# z80hb3_2021-04-01.net
KiCad netlist of a schematic drawn in EasyEDA
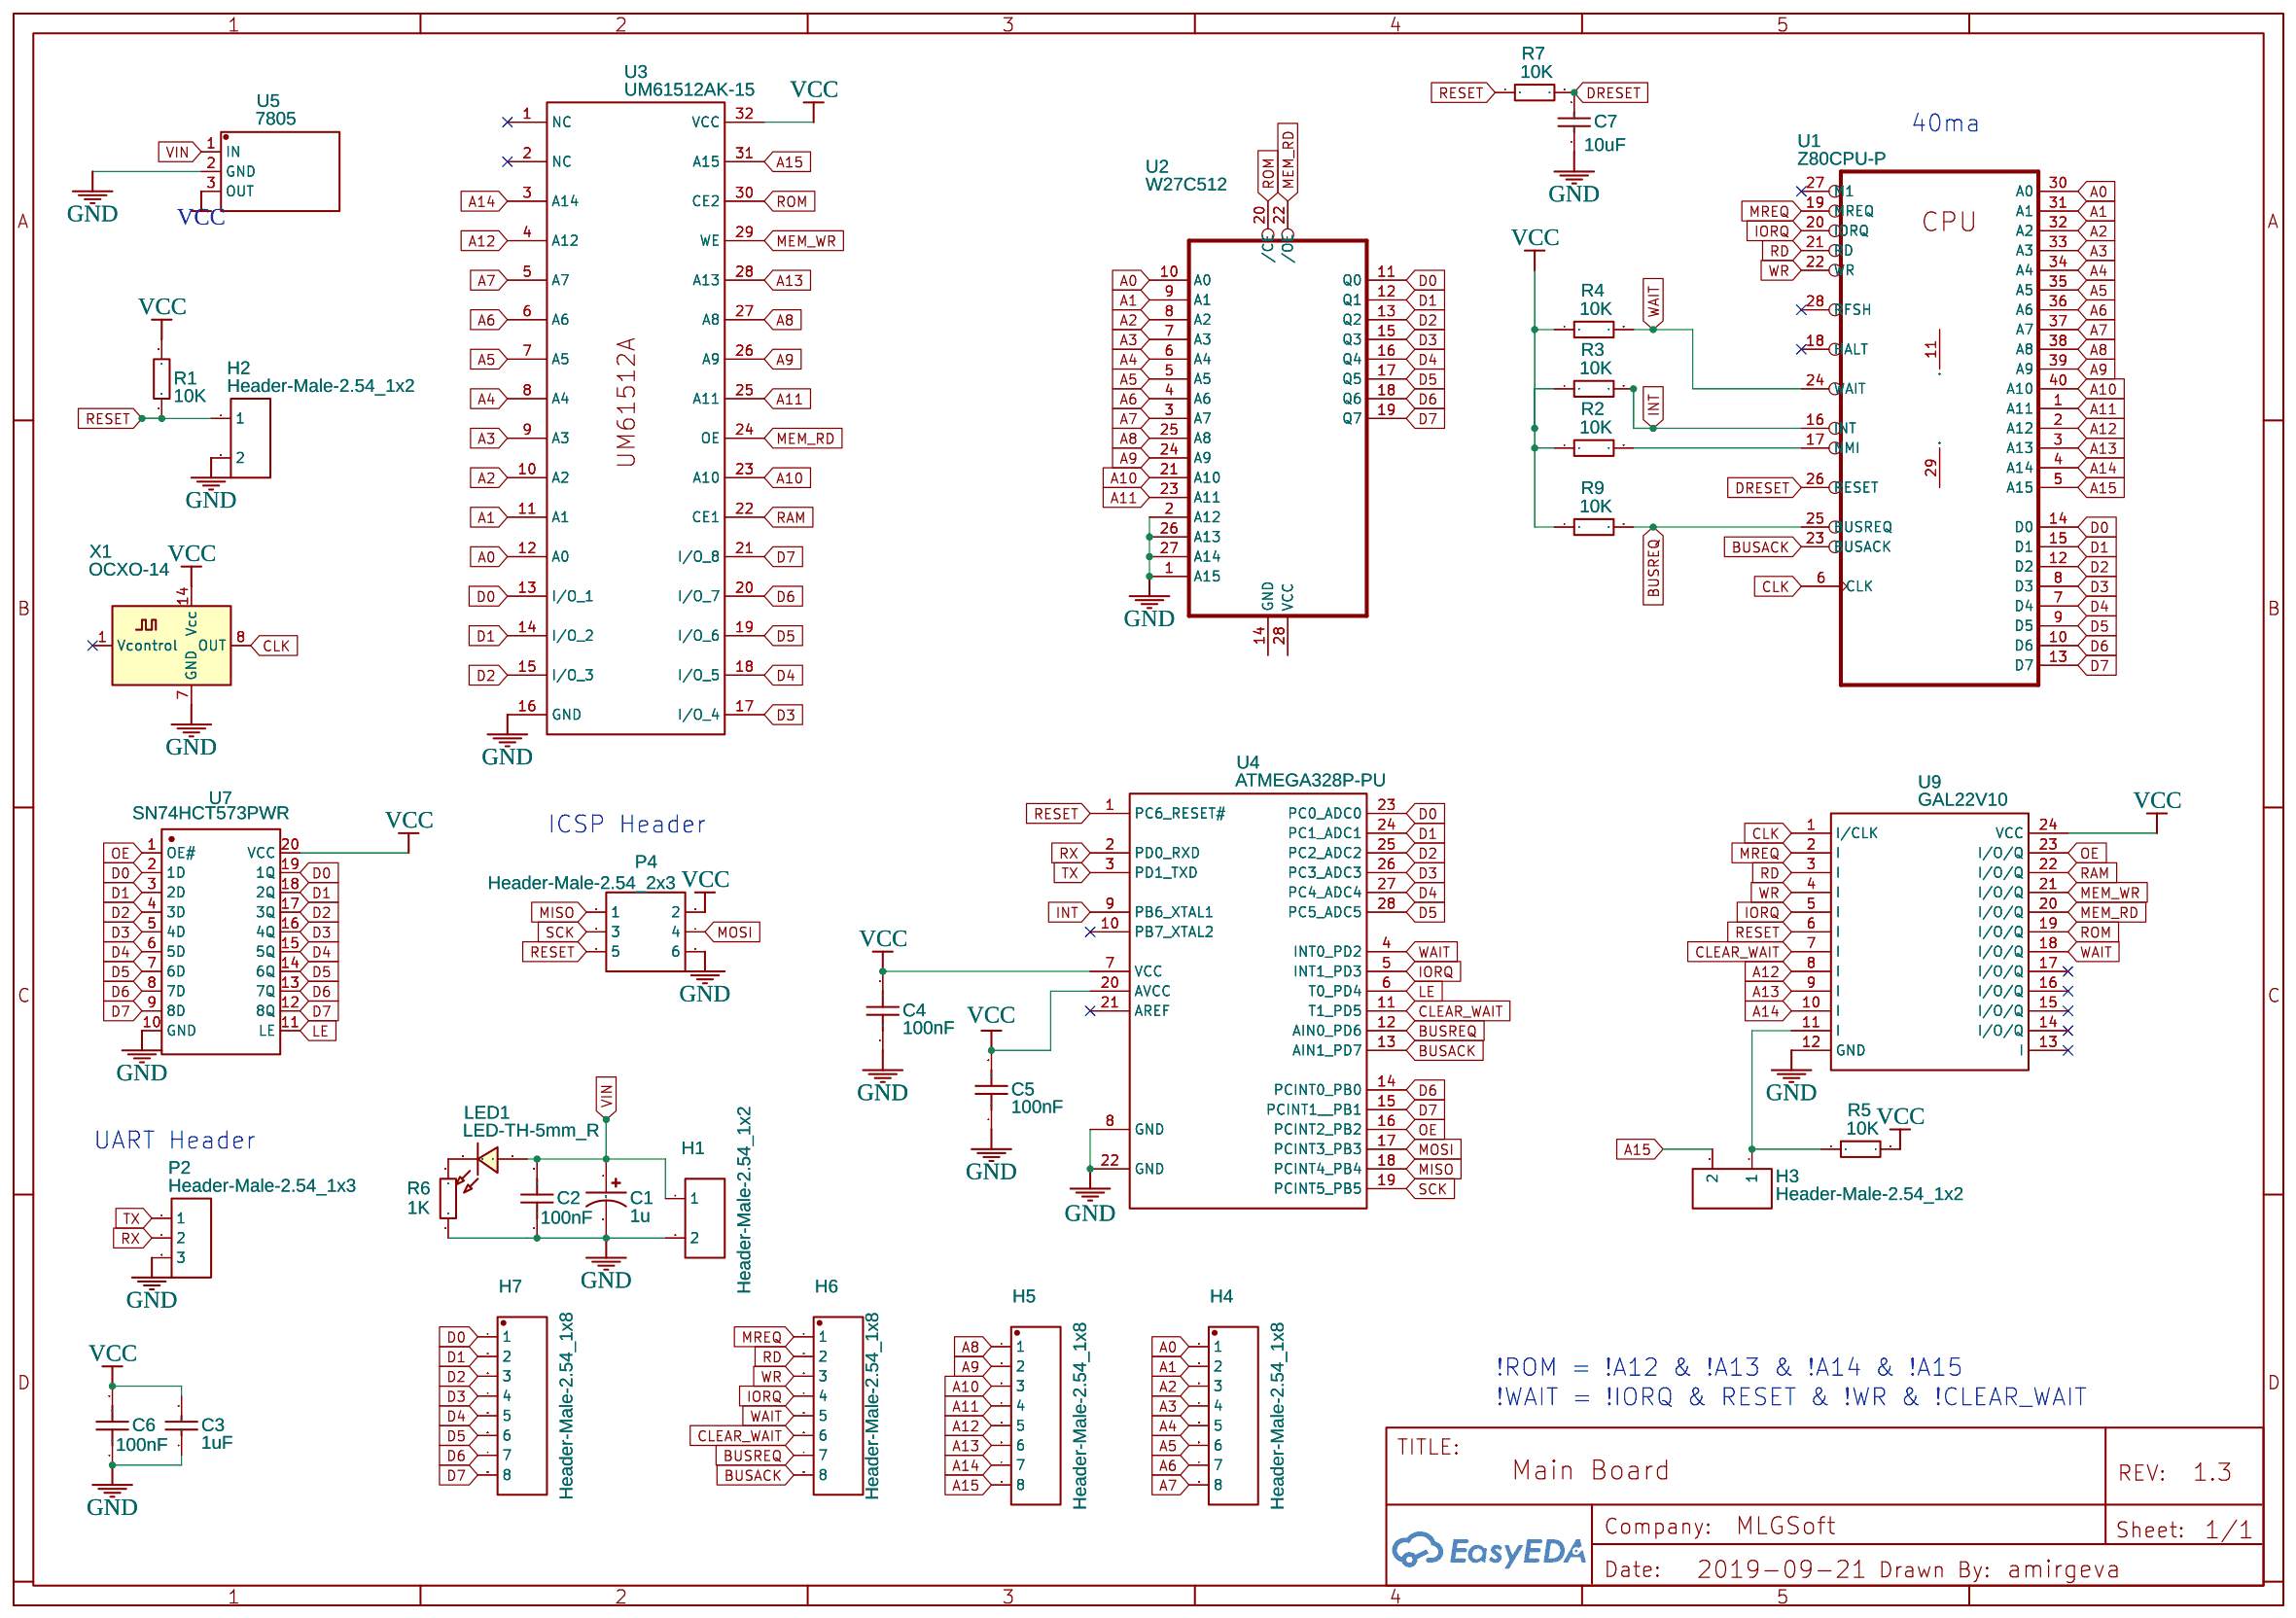
[diagram p0: schematic sheet]

(export (version "E")
  (design (tool "Eeschema 10.0.6"))
  (components
    (comp (ref "C1") (value "1u") (libsource (lib "") (part "CE_TH_D3.0×F1.5_US")))
    (comp (ref "C2")
      (value "100nF")
      (fields
        (field (name "BOM_Manufacturer Part") "0402B104K160")
        (field (name "BOM_Supplier Part") "C83056")
      )
      (libsource (lib "") (part "0402B104K160"))
    )
    (comp (ref "C3")
      (value "1uF")
      (fields
        (field (name "BOM_Manufacturer Part") "CL05A105KO5NNNC")
        (field (name "BOM_Supplier Part") "C29266")
      )
      (libsource (lib "") (part "CL05A105KO5NNNC"))
    )
    (comp (ref "C4")
      (value "100nF")
      (fields
        (field (name "BOM_Manufacturer Part") "0402B104K160")
        (field (name "BOM_Supplier Part") "C83056")
      )
      (libsource (lib "") (part "0402B104K160"))
    )
    (comp (ref "C5")
      (value "100nF")
      (fields
        (field (name "BOM_Manufacturer Part") "0402B104K160")
        (field (name "BOM_Supplier Part") "C83056")
      )
      (libsource (lib "") (part "0402B104K160"))
    )
    (comp (ref "C6")
      (value "100nF")
      (fields
        (field (name "BOM_Manufacturer Part") "0402B104K160")
        (field (name "BOM_Supplier Part") "C83056")
      )
      (libsource (lib "") (part "0402B104K160"))
    )
    (comp (ref "C7")
      (value "10uF")
      (fields
        (field (name "BOM_Manufacturer Part") "CL05A106MQ5NUNC")
        (field (name "BOM_Supplier Part") "C15525")
      )
      (libsource (lib "") (part "CL05A106MQ5NUNC"))
    )
    (comp (ref "H1")
      (value "Header-Male-2.54_1x2")
      (fields (field (name "BOM_Manufacturer Part") "826629-2") (field (name "BOM_Supplier Part") "C86471"))
      (libsource (lib "") (part "Unknown_345_610"))
    )
    (comp (ref "H2")
      (value "Header-Male-2.54_1x2")
      (fields (field (name "BOM_Manufacturer Part") "826629-2") (field (name "BOM_Supplier Part") "C86471"))
      (libsource (lib "") (part "Unknown_115_215"))
    )
    (comp (ref "H3")
      (value "Header-Male-2.54_1x2")
      (fields (field (name "BOM_Manufacturer Part") "826629-2") (field (name "BOM_Supplier Part") "C86471"))
      (libsource (lib "") (part "Unknown_870_590"))
    )
    (comp (ref "H4")
      (value "Header-Male-2.54_1x8")
      (fields
        (field (name "BOM_Manufacturer Part") "210S-1*8P L=11.6MMGold-plated black")
        (field (name "BOM_Supplier Part") "C124381")
      )
      (libsource (lib "") (part "Header-Male-2.54_1x8"))
    )
    (comp (ref "H5")
      (value "Header-Male-2.54_1x8")
      (fields
        (field (name "BOM_Manufacturer Part") "210S-1*8P L=11.6MMGold-plated black")
        (field (name "BOM_Supplier Part") "C124381")
      )
      (libsource (lib "") (part "Header-Male-2.54_1x8"))
    )
    (comp (ref "H6")
      (value "Header-Male-2.54_1x8")
      (fields
        (field (name "BOM_Manufacturer Part") "210S-1*8P L=11.6MMGold-plated black")
        (field (name "BOM_Supplier Part") "C124381")
      )
      (libsource (lib "") (part "Header-Male-2.54_1x8"))
    )
    (comp (ref "H7")
      (value "Header-Male-2.54_1x8")
      (fields
        (field (name "BOM_Manufacturer Part") "210S-1*8P L=11.6MMGold-plated black")
        (field (name "BOM_Supplier Part") "C124381")
      )
      (libsource (lib "") (part "Header-Male-2.54_1x8"))
    )
    (comp (ref "LED1")
      (value "LED-TH-5mm_R")
      (fields
        (field (name "BOM_Manufacturer Part") "333-2SURD/S530-A3")
        (field (name "BOM_Supplier Part") "C87271")
      )
      (libsource (lib "") (part "LED-TH-5mm_R"))
    )
    (comp (ref "P2")
      (value "Header-Male-2.54_1x3")
      (fields
        (field (name "BOM_Manufacturer Part") "Header2.54mm 1*3P")
        (field (name "BOM_Supplier Part") "C49257")
      )
      (libsource (lib "") (part "Unknown_85_620"))
    )
    (comp (ref "P4")
      (value "Header-Male-2.54_2x3")
      (fields (field (name "BOM_Supplier Part") "C65114"))
      (libsource (lib "") (part "Unknown_320_465"))
    )
    (comp (ref "R1")
      (value "10K")
      (fields
        (field (name "BOM_Manufacturer Part") "0402WGF1002TCE")
        (field (name "BOM_Supplier Part") "C25744")
      )
      (libsource (lib "") (part "0402WGF1002TCE_1"))
    )
    (comp (ref "R2")
      (value "10K")
      (fields
        (field (name "BOM_Manufacturer Part") "0402WGF1002TCE")
        (field (name "BOM_Supplier Part") "C25744")
      )
      (libsource (lib "") (part "0402WGF1002TCE"))
    )
    (comp (ref "R3")
      (value "10K")
      (fields
        (field (name "BOM_Manufacturer Part") "0402WGF1002TCE")
        (field (name "BOM_Supplier Part") "C25744")
      )
      (libsource (lib "") (part "0402WGF1002TCE"))
    )
    (comp (ref "R4")
      (value "10K")
      (fields
        (field (name "BOM_Manufacturer Part") "0402WGF1002TCE")
        (field (name "BOM_Supplier Part") "C25744")
      )
      (libsource (lib "") (part "0402WGF1002TCE"))
    )
    (comp (ref "R5")
      (value "10K")
      (fields
        (field (name "BOM_Manufacturer Part") "0402WGF1002TCE")
        (field (name "BOM_Supplier Part") "C25744")
      )
      (libsource (lib "") (part "0402WGF1002TCE"))
    )
    (comp (ref "R6")
      (value "1K")
      (fields
        (field (name "BOM_Manufacturer Part") "RC0402JR-071KL")
        (field (name "BOM_Supplier Part") "C105637")
      )
      (libsource (lib "") (part "RC0402JR-071KL"))
    )
    (comp (ref "R7")
      (value "10K")
      (fields
        (field (name "BOM_Manufacturer Part") "0402WGF1002TCE")
        (field (name "BOM_Supplier Part") "C25744")
      )
      (libsource (lib "") (part "0402WGF1002TCE"))
    )
    (comp (ref "R9")
      (value "10K")
      (fields
        (field (name "BOM_Manufacturer Part") "0402WGF1002TCE")
        (field (name "BOM_Supplier Part") "C25744")
      )
      (libsource (lib "") (part "0402WGF1002TCE"))
    )
    (comp (ref "U1")
      (value "Z80CPU-P")
      (fields (field (name "BOM_Manufacturer Part") "?"))
      (libsource (lib "") (part "Unknown_975_200"))
    )
    (comp (ref "U2") (value "W27C512") (libsource (lib "") (part "Unknown_635_185")))
    (comp (ref "U3") (value "UM61512AK-15") (libsource (lib "") (part "Unknown_310_215")))
    (comp (ref "U4")
      (value "ATMEGA328P-PU")
      (fields (field (name "BOM_Supplier Part") "C33901"))
      (libsource (lib "") (part "ATMEGA328P-PU"))
    )
    (comp (ref "U5")
      (value "7805")
      (fields (field (name "BOM_Supplier Part") "C305416"))
      (libsource (lib "") (part "7805"))
    )
    (comp (ref "U7")
      (value "SN74HCT573PWR")
      (fields (field (name "BOM_Supplier Part") "C141336"))
      (libsource (lib "") (part "SN74HCT573PWR"))
    )
    (comp (ref "U9") (value "GAL22V10") (libsource (lib "") (part "GAL22V10")))
    (comp (ref "X1")
      (value "OCXO-14")
      (fields (field (name "BOM_Manufacturer Part") "?"))
      (libsource (lib "") (part "Unknown_80_320"))
    )
  )
  (nets
    (net (code "1") (name "A0") (class "Default")
      (node (ref "H4") (pin "1") (pinfunction "1_1") (pintype "unspecified"))
      (node (ref "U1") (pin "30") (pinfunction "A0_30") (pintype "output"))
      (node (ref "U2") (pin "10") (pinfunction "A0_10") (pintype "input"))
      (node (ref "U3") (pin "12") (pinfunction "A0_12") (pintype "unspecified"))
    )
    (net (code "2") (name "A1") (class "Default")
      (node (ref "H4") (pin "2") (pinfunction "2_2") (pintype "unspecified"))
      (node (ref "U1") (pin "31") (pinfunction "A1_31") (pintype "output"))
      (node (ref "U2") (pin "9") (pinfunction "A1_9") (pintype "input"))
      (node (ref "U3") (pin "11") (pinfunction "A1_11") (pintype "unspecified"))
    )
    (net (code "3") (name "A2") (class "Default")
      (node (ref "H4") (pin "3") (pinfunction "3_3") (pintype "unspecified"))
      (node (ref "U1") (pin "32") (pinfunction "A2_32") (pintype "output"))
      (node (ref "U2") (pin "8") (pinfunction "A2_8") (pintype "input"))
      (node (ref "U3") (pin "10") (pinfunction "A2_10") (pintype "unspecified"))
    )
    (net (code "4") (name "A3") (class "Default")
      (node (ref "H4") (pin "4") (pinfunction "4_4") (pintype "unspecified"))
      (node (ref "U1") (pin "33") (pinfunction "A3_33") (pintype "output"))
      (node (ref "U2") (pin "7") (pinfunction "A3_7") (pintype "input"))
      (node (ref "U3") (pin "9") (pinfunction "A3_9") (pintype "unspecified"))
    )
    (net (code "5") (name "A4") (class "Default")
      (node (ref "H4") (pin "5") (pinfunction "5_5") (pintype "unspecified"))
      (node (ref "U1") (pin "34") (pinfunction "A4_34") (pintype "output"))
      (node (ref "U2") (pin "6") (pinfunction "A4_6") (pintype "input"))
      (node (ref "U3") (pin "8") (pinfunction "A4_8") (pintype "unspecified"))
    )
    (net (code "6") (name "A5") (class "Default")
      (node (ref "H4") (pin "6") (pinfunction "6_6") (pintype "unspecified"))
      (node (ref "U1") (pin "35") (pinfunction "A5_35") (pintype "output"))
      (node (ref "U2") (pin "5") (pinfunction "A5_5") (pintype "input"))
      (node (ref "U3") (pin "7") (pinfunction "A5_7") (pintype "unspecified"))
    )
    (net (code "7") (name "A6") (class "Default")
      (node (ref "H4") (pin "7") (pinfunction "7_7") (pintype "unspecified"))
      (node (ref "U1") (pin "36") (pinfunction "A6_36") (pintype "output"))
      (node (ref "U2") (pin "4") (pinfunction "A6_4") (pintype "input"))
      (node (ref "U3") (pin "6") (pinfunction "A6_6") (pintype "unspecified"))
    )
    (net (code "8") (name "A7") (class "Default")
      (node (ref "H4") (pin "8") (pinfunction "8_8") (pintype "unspecified"))
      (node (ref "U1") (pin "37") (pinfunction "A7_37") (pintype "output"))
      (node (ref "U2") (pin "3") (pinfunction "A7_3") (pintype "input"))
      (node (ref "U3") (pin "5") (pinfunction "A7_5") (pintype "unspecified"))
    )
    (net (code "9") (name "A8") (class "Default")
      (node (ref "H5") (pin "1") (pinfunction "1_1") (pintype "unspecified"))
      (node (ref "U1") (pin "38") (pinfunction "A8_38") (pintype "output"))
      (node (ref "U2") (pin "25") (pinfunction "A8_25") (pintype "input"))
      (node (ref "U3") (pin "27") (pinfunction "A8_27") (pintype "unspecified"))
    )
    (net (code "10") (name "A9") (class "Default")
      (node (ref "H5") (pin "2") (pinfunction "2_2") (pintype "unspecified"))
      (node (ref "U1") (pin "39") (pinfunction "A9_39") (pintype "output"))
      (node (ref "U2") (pin "24") (pinfunction "A9_24") (pintype "input"))
      (node (ref "U3") (pin "26") (pinfunction "A9_26") (pintype "unspecified"))
    )
    (net (code "11") (name "A10") (class "Default")
      (node (ref "H5") (pin "3") (pinfunction "3_3") (pintype "unspecified"))
      (node (ref "U1") (pin "40") (pinfunction "A10_40") (pintype "output"))
      (node (ref "U2") (pin "21") (pinfunction "A10_21") (pintype "input"))
      (node (ref "U3") (pin "23") (pinfunction "A10_23") (pintype "unspecified"))
    )
    (net (code "12") (name "A11") (class "Default")
      (node (ref "H5") (pin "4") (pinfunction "4_4") (pintype "unspecified"))
      (node (ref "U1") (pin "1") (pinfunction "A11_1") (pintype "output"))
      (node (ref "U2") (pin "23") (pinfunction "A11_23") (pintype "input"))
      (node (ref "U3") (pin "25") (pinfunction "A11_25") (pintype "unspecified"))
    )
    (net (code "13") (name "A12") (class "Default")
      (node (ref "H5") (pin "5") (pinfunction "5_5") (pintype "unspecified"))
      (node (ref "U1") (pin "2") (pinfunction "A12_2") (pintype "output"))
      (node (ref "U3") (pin "4") (pinfunction "A12_4") (pintype "unspecified"))
      (node (ref "U9") (pin "8") (pinfunction "I_8") (pintype "unspecified"))
    )
    (net (code "14") (name "A13") (class "Default")
      (node (ref "H5") (pin "6") (pinfunction "6_6") (pintype "unspecified"))
      (node (ref "U1") (pin "3") (pinfunction "A13_3") (pintype "output"))
      (node (ref "U3") (pin "28") (pinfunction "A13_28") (pintype "unspecified"))
      (node (ref "U9") (pin "9") (pinfunction "I_9") (pintype "unspecified"))
    )
    (net (code "15") (name "A14") (class "Default")
      (node (ref "H5") (pin "7") (pinfunction "7_7") (pintype "unspecified"))
      (node (ref "U1") (pin "4") (pinfunction "A14_4") (pintype "output"))
      (node (ref "U3") (pin "3") (pinfunction "A14_3") (pintype "unspecified"))
      (node (ref "U9") (pin "10") (pinfunction "I_10") (pintype "unspecified"))
    )
    (net (code "16") (name "A15") (class "Default")
      (node (ref "H3") (pin "2") (pinfunction "2_2") (pintype "unspecified"))
      (node (ref "H5") (pin "8") (pinfunction "8_8") (pintype "unspecified"))
      (node (ref "U1") (pin "5") (pinfunction "A15_5") (pintype "output"))
      (node (ref "U3") (pin "31") (pinfunction "A15_31") (pintype "unspecified"))
    )
    (net (code "17") (name "BUSACK") (class "Default")
      (node (ref "H6") (pin "8") (pinfunction "8_8") (pintype "unspecified"))
      (node (ref "U1") (pin "23") (pinfunction "BUSACK_23") (pintype "output"))
      (node (ref "U4") (pin "13") (pinfunction "AIN1_PD7_13") (pintype "bidirectional"))
    )
    (net (code "18") (name "BUSREQ") (class "Default")
      (node (ref "H6") (pin "7") (pinfunction "7_7") (pintype "unspecified"))
      (node (ref "R9") (pin "2") (pinfunction "2_2") (pintype "input"))
      (node (ref "U1") (pin "25") (pinfunction "BUSREQ_25") (pintype "input"))
      (node (ref "U4") (pin "12") (pinfunction "AIN0_PD6_12") (pintype "bidirectional"))
    )
    (net (code "19") (name "CLEAR_WAIT") (class "Default")
      (node (ref "H6") (pin "6") (pinfunction "6_6") (pintype "unspecified"))
      (node (ref "U4") (pin "11") (pinfunction "T1_PD5_11") (pintype "bidirectional"))
      (node (ref "U9") (pin "7") (pinfunction "I_7") (pintype "unspecified"))
    )
    (net (code "20") (name "CLK") (class "Default")
      (node (ref "U1") (pin "6") (pinfunction "CLK_6") (pintype "input"))
      (node (ref "U9") (pin "1") (pinfunction "I/CLK_1") (pintype "unspecified"))
      (node (ref "X1") (pin "8") (pinfunction "OUT_8") (pintype "output"))
    )
    (net (code "21") (name "D0") (class "Default")
      (node (ref "H7") (pin "1") (pinfunction "1_1") (pintype "unspecified"))
      (node (ref "U1") (pin "14") (pinfunction "D0_14") (pintype "unspecified"))
      (node (ref "U2") (pin "11") (pinfunction "Q0_11") (pintype "bidirectional"))
      (node (ref "U3") (pin "13") (pinfunction "I/O_1_13") (pintype "unspecified"))
      (node (ref "U4") (pin "23") (pinfunction "PC0_ADC0_23") (pintype "bidirectional"))
      (node (ref "U7") (pin "19") (pinfunction "1Q_19") (pintype "unspecified"))
      (node (ref "U7") (pin "2") (pinfunction "1D_2") (pintype "unspecified"))
    )
    (net (code "22") (name "D1") (class "Default")
      (node (ref "H7") (pin "2") (pinfunction "2_2") (pintype "unspecified"))
      (node (ref "U1") (pin "15") (pinfunction "D1_15") (pintype "unspecified"))
      (node (ref "U2") (pin "12") (pinfunction "Q1_12") (pintype "bidirectional"))
      (node (ref "U3") (pin "14") (pinfunction "I/O_2_14") (pintype "unspecified"))
      (node (ref "U4") (pin "24") (pinfunction "PC1_ADC1_24") (pintype "bidirectional"))
      (node (ref "U7") (pin "18") (pinfunction "2Q_18") (pintype "unspecified"))
      (node (ref "U7") (pin "3") (pinfunction "2D_3") (pintype "unspecified"))
    )
    (net (code "23") (name "D2") (class "Default")
      (node (ref "H7") (pin "3") (pinfunction "3_3") (pintype "unspecified"))
      (node (ref "U1") (pin "12") (pinfunction "D2_12") (pintype "unspecified"))
      (node (ref "U2") (pin "13") (pinfunction "Q2_13") (pintype "bidirectional"))
      (node (ref "U3") (pin "15") (pinfunction "I/O_3_15") (pintype "unspecified"))
      (node (ref "U4") (pin "25") (pinfunction "PC2_ADC2_25") (pintype "bidirectional"))
      (node (ref "U7") (pin "17") (pinfunction "3Q_17") (pintype "unspecified"))
      (node (ref "U7") (pin "4") (pinfunction "3D_4") (pintype "unspecified"))
    )
    (net (code "24") (name "D3") (class "Default")
      (node (ref "H7") (pin "4") (pinfunction "4_4") (pintype "unspecified"))
      (node (ref "U1") (pin "8") (pinfunction "D3_8") (pintype "unspecified"))
      (node (ref "U2") (pin "15") (pinfunction "Q3_15") (pintype "bidirectional"))
      (node (ref "U3") (pin "17") (pinfunction "I/O_4_17") (pintype "unspecified"))
      (node (ref "U4") (pin "26") (pinfunction "PC3_ADC3_26") (pintype "bidirectional"))
      (node (ref "U7") (pin "16") (pinfunction "4Q_16") (pintype "unspecified"))
      (node (ref "U7") (pin "5") (pinfunction "4D_5") (pintype "unspecified"))
    )
    (net (code "25") (name "D4") (class "Default")
      (node (ref "H7") (pin "5") (pinfunction "5_5") (pintype "unspecified"))
      (node (ref "U1") (pin "7") (pinfunction "D4_7") (pintype "unspecified"))
      (node (ref "U2") (pin "16") (pinfunction "Q4_16") (pintype "bidirectional"))
      (node (ref "U3") (pin "18") (pinfunction "I/O_5_18") (pintype "unspecified"))
      (node (ref "U4") (pin "27") (pinfunction "PC4_ADC4_27") (pintype "bidirectional"))
      (node (ref "U7") (pin "15") (pinfunction "5Q_15") (pintype "unspecified"))
      (node (ref "U7") (pin "6") (pinfunction "5D_6") (pintype "unspecified"))
    )
    (net (code "26") (name "D5") (class "Default")
      (node (ref "H7") (pin "6") (pinfunction "6_6") (pintype "unspecified"))
      (node (ref "U1") (pin "9") (pinfunction "D5_9") (pintype "unspecified"))
      (node (ref "U2") (pin "17") (pinfunction "Q5_17") (pintype "bidirectional"))
      (node (ref "U3") (pin "19") (pinfunction "I/O_6_19") (pintype "unspecified"))
      (node (ref "U4") (pin "28") (pinfunction "PC5_ADC5_28") (pintype "bidirectional"))
      (node (ref "U7") (pin "14") (pinfunction "6Q_14") (pintype "unspecified"))
      (node (ref "U7") (pin "7") (pinfunction "6D_7") (pintype "unspecified"))
    )
    (net (code "27") (name "D6") (class "Default")
      (node (ref "H7") (pin "7") (pinfunction "7_7") (pintype "unspecified"))
      (node (ref "U1") (pin "10") (pinfunction "D6_10") (pintype "unspecified"))
      (node (ref "U2") (pin "18") (pinfunction "Q6_18") (pintype "bidirectional"))
      (node (ref "U3") (pin "20") (pinfunction "I/O_7_20") (pintype "unspecified"))
      (node (ref "U4") (pin "14") (pinfunction "PCINT0_PB0_14") (pintype "bidirectional"))
      (node (ref "U7") (pin "13") (pinfunction "7Q_13") (pintype "unspecified"))
      (node (ref "U7") (pin "8") (pinfunction "7D_8") (pintype "unspecified"))
    )
    (net (code "28") (name "D7") (class "Default")
      (node (ref "H7") (pin "8") (pinfunction "8_8") (pintype "unspecified"))
      (node (ref "U1") (pin "13") (pinfunction "D7_13") (pintype "unspecified"))
      (node (ref "U2") (pin "19") (pinfunction "Q7_19") (pintype "bidirectional"))
      (node (ref "U3") (pin "21") (pinfunction "I/O_8_21") (pintype "unspecified"))
      (node (ref "U4") (pin "15") (pinfunction "PCINT1__PB1_15") (pintype "bidirectional"))
      (node (ref "U7") (pin "12") (pinfunction "8Q_12") (pintype "unspecified"))
      (node (ref "U7") (pin "9") (pinfunction "8D_9") (pintype "unspecified"))
    )
    (net (code "29") (name "DRESET") (class "Default")
      (node (ref "C7") (pin "2") (pinfunction "2_2") (pintype "input"))
      (node (ref "R7") (pin "2") (pinfunction "2_2") (pintype "input"))
      (node (ref "U1") (pin "26") (pinfunction "RESET_26") (pintype "input"))
    )
    (net (code "30") (name "GND") (class "Default")
      (node (ref "C1") (pin "2") (pinfunction "2_2") (pintype "unspecified"))
      (node (ref "C2") (pin "1") (pinfunction "1_1") (pintype "unspecified"))
      (node (ref "C3") (pin "1") (pinfunction "1_1") (pintype "input"))
      (node (ref "C4") (pin "1") (pinfunction "1_1") (pintype "unspecified"))
      (node (ref "C5") (pin "1") (pinfunction "1_1") (pintype "unspecified"))
      (node (ref "C6") (pin "1") (pinfunction "1_1") (pintype "unspecified"))
      (node (ref "C7") (pin "1") (pinfunction "1_1") (pintype "input"))
      (node (ref "H1") (pin "2") (pinfunction "2_2") (pintype "unspecified"))
      (node (ref "H2") (pin "2") (pinfunction "2_2") (pintype "unspecified"))
      (node (ref "P2") (pin "3") (pinfunction "3_3") (pintype "input"))
      (node (ref "P4") (pin "6") (pinfunction "6_6") (pintype "input"))
      (node (ref "R6") (pin "1") (pinfunction "1_1") (pintype "input"))
      (node (ref "U2") (pin "1") (pinfunction "A15_1") (pintype "input"))
      (node (ref "U2") (pin "2") (pinfunction "A12_2") (pintype "input"))
      (node (ref "U2") (pin "26") (pinfunction "A13_26") (pintype "input"))
      (node (ref "U2") (pin "27") (pinfunction "A14_27") (pintype "input"))
      (node (ref "U3") (pin "16") (pinfunction "GND_16") (pintype "unspecified"))
      (node (ref "U4") (pin "22") (pinfunction "GND_22") (pintype "passive"))
      (node (ref "U4") (pin "8") (pinfunction "GND_8") (pintype "passive"))
      (node (ref "U5") (pin "2") (pinfunction "GND_2") (pintype "unspecified"))
      (node (ref "U7") (pin "10") (pinfunction "GND_10") (pintype "unspecified"))
      (node (ref "U9") (pin "12") (pinfunction "GND_12") (pintype "unspecified"))
      (node (ref "X1") (pin "7") (pinfunction "GND_7") (pintype "bidirectional"))
    )
    (net (code "31") (name "INT") (class "Default")
      (node (ref "R3") (pin "2") (pinfunction "2_2") (pintype "input"))
      (node (ref "U1") (pin "16") (pinfunction "INT_16") (pintype "input"))
      (node (ref "U4") (pin "9") (pinfunction "PB6_XTAL1_9") (pintype "bidirectional"))
    )
    (net (code "32") (name "IORQ") (class "Default")
      (node (ref "H6") (pin "4") (pinfunction "4_4") (pintype "unspecified"))
      (node (ref "U1") (pin "20") (pinfunction "IORQ_20") (pintype "output"))
      (node (ref "U4") (pin "5") (pinfunction "INT1_PD3_5") (pintype "bidirectional"))
      (node (ref "U9") (pin "5") (pinfunction "I_5") (pintype "unspecified"))
    )
    (net (code "33") (name "LE") (class "Default")
      (node (ref "U4") (pin "6") (pinfunction "T0_PD4_6") (pintype "bidirectional"))
      (node (ref "U7") (pin "11") (pinfunction "LE_11") (pintype "unspecified"))
    )
    (net (code "34") (name "MEM_RD") (class "Default")
      (node (ref "U2") (pin "22") (pinfunction "/OE_22") (pintype "input"))
      (node (ref "U3") (pin "24") (pinfunction "OE_24") (pintype "unspecified"))
      (node (ref "U9") (pin "20") (pinfunction "I/O/Q_20") (pintype "unspecified"))
    )
    (net (code "35") (name "MEM_WR") (class "Default")
      (node (ref "U3") (pin "29") (pinfunction "WE_29") (pintype "unspecified"))
      (node (ref "U9") (pin "21") (pinfunction "I/O/Q_21") (pintype "unspecified"))
    )
    (net (code "36") (name "MISO") (class "Default")
      (node (ref "P4") (pin "1") (pinfunction "1_1") (pintype "input"))
      (node (ref "U4") (pin "18") (pinfunction "PCINT4_PB4_18") (pintype "bidirectional"))
    )
    (net (code "37") (name "MOSI") (class "Default")
      (node (ref "P4") (pin "4") (pinfunction "4_4") (pintype "input"))
      (node (ref "U4") (pin "17") (pinfunction "PCINT3_PB3_17") (pintype "bidirectional"))
    )
    (net (code "38") (name "MREQ") (class "Default")
      (node (ref "H6") (pin "1") (pinfunction "1_1") (pintype "unspecified"))
      (node (ref "U1") (pin "19") (pinfunction "MREQ_19") (pintype "output"))
      (node (ref "U9") (pin "2") (pinfunction "I_2") (pintype "unspecified"))
    )
    (net (code "39") (name "Net-(H3-Pad1)") (class "Default")
      (node (ref "H3") (pin "1") (pinfunction "1_1") (pintype "unspecified"))
      (node (ref "R5") (pin "1") (pinfunction "1_1") (pintype "input"))
      (node (ref "U9") (pin "11") (pinfunction "I_11") (pintype "unspecified"))
    )
    (net (code "40") (name "Net-(LED1-Pad2)") (class "Default")
      (node (ref "LED1") (pin "2") (pinfunction "2_2") (pintype "unspecified"))
      (node (ref "R6") (pin "2") (pinfunction "2_2") (pintype "input"))
    )
    (net (code "41") (name "Net-(U1-NMI)") (class "Default")
      (node (ref "R2") (pin "2") (pinfunction "2_2") (pintype "input"))
      (node (ref "U1") (pin "17") (pinfunction "NMI_17") (pintype "input"))
    )
    (net (code "42") (name "OE") (class "Default")
      (node (ref "U4") (pin "16") (pinfunction "PCINT2_PB2_16") (pintype "bidirectional"))
      (node (ref "U7") (pin "1") (pinfunction "OE#_1") (pintype "unspecified"))
      (node (ref "U9") (pin "23") (pinfunction "I/O/Q_23") (pintype "unspecified"))
    )
    (net (code "43") (name "RAM") (class "Default")
      (node (ref "U3") (pin "22") (pinfunction "CE1_22") (pintype "unspecified"))
      (node (ref "U9") (pin "22") (pinfunction "I/O/Q_22") (pintype "unspecified"))
    )
    (net (code "44") (name "RD") (class "Default")
      (node (ref "H6") (pin "2") (pinfunction "2_2") (pintype "unspecified"))
      (node (ref "U1") (pin "21") (pinfunction "RD_21") (pintype "output"))
      (node (ref "U9") (pin "3") (pinfunction "I_3") (pintype "unspecified"))
    )
    (net (code "45") (name "RESET") (class "Default")
      (node (ref "H2") (pin "1") (pinfunction "1_1") (pintype "unspecified"))
      (node (ref "P4") (pin "5") (pinfunction "5_5") (pintype "input"))
      (node (ref "R1") (pin "1") (pinfunction "1_1") (pintype "input"))
      (node (ref "R7") (pin "1") (pinfunction "1_1") (pintype "input"))
      (node (ref "U4") (pin "1") (pinfunction "PC6_RESET#_1") (pintype "bidirectional"))
      (node (ref "U9") (pin "6") (pinfunction "I_6") (pintype "unspecified"))
    )
    (net (code "46") (name "ROM") (class "Default")
      (node (ref "U2") (pin "20") (pinfunction "/CE_20") (pintype "input"))
      (node (ref "U3") (pin "30") (pinfunction "CE2_30") (pintype "unspecified"))
      (node (ref "U9") (pin "19") (pinfunction "I/O/Q_19") (pintype "unspecified"))
    )
    (net (code "47") (name "RX") (class "Default")
      (node (ref "P2") (pin "2") (pinfunction "2_2") (pintype "input"))
      (node (ref "U4") (pin "2") (pinfunction "PD0_RXD_2") (pintype "bidirectional"))
    )
    (net (code "48") (name "SCK") (class "Default")
      (node (ref "P4") (pin "3") (pinfunction "3_3") (pintype "input"))
      (node (ref "U4") (pin "19") (pinfunction "PCINT5_PB5_19") (pintype "bidirectional"))
    )
    (net (code "49") (name "TX") (class "Default")
      (node (ref "P2") (pin "1") (pinfunction "1_1") (pintype "input"))
      (node (ref "U4") (pin "3") (pinfunction "PD1_TXD_3") (pintype "bidirectional"))
    )
    (net (code "50") (name "VCC") (class "Default")
      (node (ref "C3") (pin "2") (pinfunction "2_2") (pintype "input"))
      (node (ref "C4") (pin "2") (pinfunction "2_2") (pintype "unspecified"))
      (node (ref "C5") (pin "2") (pinfunction "2_2") (pintype "unspecified"))
      (node (ref "C6") (pin "2") (pinfunction "2_2") (pintype "unspecified"))
      (node (ref "P4") (pin "2") (pinfunction "2_2") (pintype "input"))
      (node (ref "R1") (pin "2") (pinfunction "2_2") (pintype "input"))
      (node (ref "R2") (pin "1") (pinfunction "1_1") (pintype "input"))
      (node (ref "R3") (pin "1") (pinfunction "1_1") (pintype "input"))
      (node (ref "R4") (pin "1") (pinfunction "1_1") (pintype "input"))
      (node (ref "R5") (pin "2") (pinfunction "2_2") (pintype "input"))
      (node (ref "R9") (pin "1") (pinfunction "1_1") (pintype "input"))
      (node (ref "U3") (pin "32") (pinfunction "VCC_32") (pintype "passive"))
      (node (ref "U4") (pin "20") (pinfunction "AVCC_20") (pintype "passive"))
      (node (ref "U4") (pin "7") (pinfunction "VCC_7") (pintype "passive"))
      (node (ref "U5") (pin "3") (pinfunction "OUT_3") (pintype "unspecified"))
      (node (ref "U7") (pin "20") (pinfunction "VCC_20") (pintype "unspecified"))
      (node (ref "U9") (pin "24") (pinfunction "VCC_24") (pintype "unspecified"))
      (node (ref "X1") (pin "14") (pinfunction "Vcc_14") (pintype "bidirectional"))
    )
    (net (code "51") (name "VIN") (class "Default")
      (node (ref "C1") (pin "1") (pinfunction "1_1") (pintype "unspecified"))
      (node (ref "C2") (pin "2") (pinfunction "2_2") (pintype "unspecified"))
      (node (ref "H1") (pin "1") (pinfunction "1_1") (pintype "unspecified"))
      (node (ref "LED1") (pin "1") (pinfunction "1_1") (pintype "unspecified"))
      (node (ref "U5") (pin "1") (pinfunction "IN_1") (pintype "unspecified"))
    )
    (net (code "52") (name "WAIT") (class "Default")
      (node (ref "H6") (pin "5") (pinfunction "5_5") (pintype "unspecified"))
      (node (ref "R4") (pin "2") (pinfunction "2_2") (pintype "input"))
      (node (ref "U1") (pin "24") (pinfunction "WAIT_24") (pintype "input"))
      (node (ref "U4") (pin "4") (pinfunction "INT0_PD2_4") (pintype "bidirectional"))
      (node (ref "U9") (pin "18") (pinfunction "I/O/Q_18") (pintype "unspecified"))
    )
    (net (code "53") (name "WR") (class "Default")
      (node (ref "H6") (pin "3") (pinfunction "3_3") (pintype "unspecified"))
      (node (ref "U1") (pin "22") (pinfunction "WR_22") (pintype "output"))
      (node (ref "U9") (pin "4") (pinfunction "I_4") (pintype "unspecified"))
    )
    (net (code "54") (name "unconnected-(U1-GND-Pad29)") (class "Default")
      (node (ref "U1") (pin "29") (pinfunction "GND_29") (pintype "passive"))
    )
    (net (code "55") (name "unconnected-(U1-HALT-Pad18)") (class "Default")
      (node (ref "U1") (pin "18") (pinfunction "HALT_18") (pintype "output+no_connect"))
    )
    (net (code "56") (name "unconnected-(U1-M1-Pad27)") (class "Default")
      (node (ref "U1") (pin "27") (pinfunction "M1_27") (pintype "output+no_connect"))
    )
    (net (code "57") (name "unconnected-(U1-RFSH-Pad28)") (class "Default")
      (node (ref "U1") (pin "28") (pinfunction "RFSH_28") (pintype "output+no_connect"))
    )
    (net (code "58") (name "unconnected-(U1-VCC-Pad11)") (class "Default")
      (node (ref "U1") (pin "11") (pinfunction "VCC_11") (pintype "passive"))
    )
    (net (code "59") (name "unconnected-(U2-GND-Pad14)") (class "Default")
      (node (ref "U2") (pin "14") (pinfunction "GND_14") (pintype "passive"))
    )
    (net (code "60") (name "unconnected-(U2-VCC-Pad28)") (class "Default")
      (node (ref "U2") (pin "28") (pinfunction "VCC_28") (pintype "passive"))
    )
    (net (code "61") (name "unconnected-(U3-NC-Pad1)") (class "Default")
      (node (ref "U3") (pin "1") (pinfunction "NC_1") (pintype "unspecified+no_connect"))
    )
    (net (code "62") (name "unconnected-(U3-NC-Pad2)") (class "Default")
      (node (ref "U3") (pin "2") (pinfunction "NC_2") (pintype "unspecified+no_connect"))
    )
    (net (code "63") (name "unconnected-(U4-AREF-Pad21)") (class "Default")
      (node (ref "U4") (pin "21") (pinfunction "AREF_21") (pintype "passive+no_connect"))
    )
    (net (code "64") (name "unconnected-(U4-PB7_XTAL2-Pad10)") (class "Default")
      (node (ref "U4") (pin "10") (pinfunction "PB7_XTAL2_10") (pintype "bidirectional+no_connect"))
    )
    (net (code "65") (name "unconnected-(U9-I-Pad13)") (class "Default")
      (node (ref "U9") (pin "13") (pinfunction "I_13") (pintype "unspecified+no_connect"))
    )
    (net (code "66") (name "unconnected-(U9-I{slash}O{slash}Q-Pad14)") (class "Default")
      (node (ref "U9") (pin "14") (pinfunction "I/O/Q_14") (pintype "unspecified+no_connect"))
    )
    (net (code "67") (name "unconnected-(U9-I{slash}O{slash}Q-Pad15)") (class "Default")
      (node (ref "U9") (pin "15") (pinfunction "I/O/Q_15") (pintype "unspecified+no_connect"))
    )
    (net (code "68") (name "unconnected-(U9-I{slash}O{slash}Q-Pad16)") (class "Default")
      (node (ref "U9") (pin "16") (pinfunction "I/O/Q_16") (pintype "unspecified+no_connect"))
    )
    (net (code "69") (name "unconnected-(U9-I{slash}O{slash}Q-Pad17)") (class "Default")
      (node (ref "U9") (pin "17") (pinfunction "I/O/Q_17") (pintype "unspecified+no_connect"))
    )
    (net (code "70") (name "unconnected-(X1-Vcontrol-Pad1)") (class "Default")
      (node (ref "X1") (pin "1") (pinfunction "Vcontrol_1") (pintype "input+no_connect"))
    )
  )
)
